# 5082_7415_mk1_v1.net
KiCad netlist of a schematic drawn in EAGLE
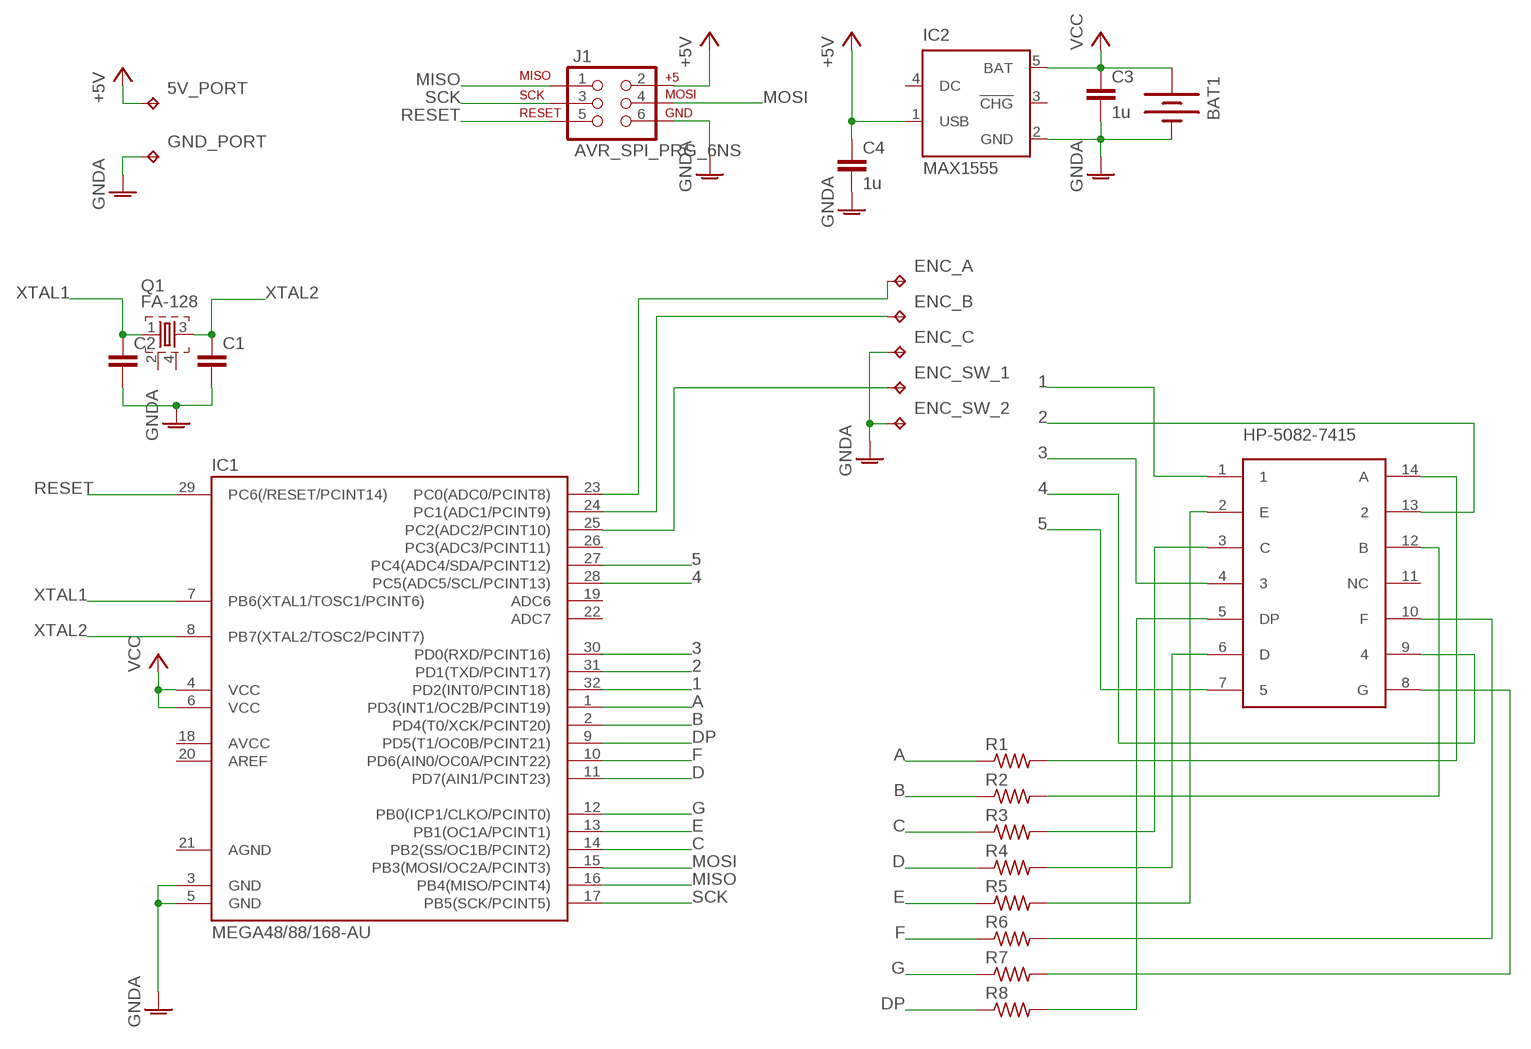
[diagram p0: schematic, sheet 1]

(export (version "E")
  (design (tool "Eeschema 10.0.6"))
  (components
    (comp (ref "5V_PORT")
      (value "TPB2,54")
      (footprint "eagle-import:B2,54")
      (libsource (lib "eagle-import") (part "TPB2,54"))
    )
    (comp (ref "BAT1")
      (value "BATTERY245MM")
      (footprint "eagle-import:BATTCON_245MM")
      (libsource (lib "eagle-import") (part "BATTERY245MM"))
    )
    (comp (ref "C1")
      (value "C-EUC0805")
      (footprint "eagle-import:C0805")
      (libsource (lib "eagle-import") (part "C-EUC0805"))
    )
    (comp (ref "C2")
      (value "C-EUC0805")
      (footprint "eagle-import:C0805")
      (libsource (lib "eagle-import") (part "C-EUC0805"))
    )
    (comp (ref "C3")
      (value "1u")
      (footprint "eagle-import:C0805")
      (libsource (lib "eagle-import") (part "C-EUC0805"))
    )
    (comp (ref "C4")
      (value "1u")
      (footprint "eagle-import:C0805")
      (libsource (lib "eagle-import") (part "C-EUC0805"))
    )
    (comp (ref "ENC_A")
      (value "TPTP20SQ")
      (footprint "eagle-import:TP20SQ")
      (libsource (lib "eagle-import") (part "TPTP20SQ"))
    )
    (comp (ref "ENC_B")
      (value "TPTP20SQ")
      (footprint "eagle-import:TP20SQ")
      (libsource (lib "eagle-import") (part "TPTP20SQ"))
    )
    (comp (ref "ENC_C")
      (value "TPTP20SQ")
      (footprint "eagle-import:TP20SQ")
      (libsource (lib "eagle-import") (part "TPTP20SQ"))
    )
    (comp (ref "ENC_SW_1")
      (value "TPTP20SQ")
      (footprint "eagle-import:TP20SQ")
      (libsource (lib "eagle-import") (part "TPTP20SQ"))
    )
    (comp (ref "ENC_SW_2")
      (value "TPTP20SQ")
      (footprint "eagle-import:TP20SQ")
      (libsource (lib "eagle-import") (part "TPTP20SQ"))
    )
    (comp (ref "GND_PORT")
      (value "TPB2,54")
      (footprint "eagle-import:B2,54")
      (libsource (lib "eagle-import") (part "TPB2,54"))
    )
    (comp (ref "IC1")
      (value "MEGA48/88/168-AU")
      (footprint "eagle-import:TQFP32-08")
      (libsource (lib "eagle-import") (part "MEGA48/88/168-AU"))
    )
    (comp (ref "IC2")
      (value "MAX1555")
      (footprint "eagle-import:SOT23-5L")
      (fields (field (name "MF") "MAXIM") (field (name "MPN") "MAX1555EZK+T"))
      (libsource (lib "eagle-import") (part "MAX1555"))
    )
    (comp (ref "J1")
      (value "AVR_SPI_PRG_6NS")
      (footprint "eagle-import:2X3-NS")
      (libsource (lib "eagle-import") (part "AVR_SPI_PRG_6NS"))
    )
    (comp (ref "Q1")
      (value "FA-128")
      (footprint "eagle-import:FA-128")
      (libsource (lib "eagle-import") (part "FA-128"))
    )
    (comp (ref "R1")
      (value "R-US_M0805")
      (footprint "eagle-import:M0805")
      (libsource (lib "eagle-import") (part "R-US_M0805"))
    )
    (comp (ref "R2")
      (value "R-US_M0805")
      (footprint "eagle-import:M0805")
      (libsource (lib "eagle-import") (part "R-US_M0805"))
    )
    (comp (ref "R3")
      (value "R-US_M0805")
      (footprint "eagle-import:M0805")
      (libsource (lib "eagle-import") (part "R-US_M0805"))
    )
    (comp (ref "R4")
      (value "R-US_M0805")
      (footprint "eagle-import:M0805")
      (libsource (lib "eagle-import") (part "R-US_M0805"))
    )
    (comp (ref "R5")
      (value "R-US_M0805")
      (footprint "eagle-import:M0805")
      (libsource (lib "eagle-import") (part "R-US_M0805"))
    )
    (comp (ref "R6")
      (value "R-US_M0805")
      (footprint "eagle-import:M0805")
      (libsource (lib "eagle-import") (part "R-US_M0805"))
    )
    (comp (ref "R7")
      (value "R-US_M0805")
      (footprint "eagle-import:M0805")
      (libsource (lib "eagle-import") (part "R-US_M0805"))
    )
    (comp (ref "R8")
      (value "R-US_M0805")
      (footprint "eagle-import:M0805")
      (libsource (lib "eagle-import") (part "R-US_M0805"))
    )
    (comp (ref "U$1")
      (value "HP-5082-7415")
      (footprint "eagle-import:DIL14")
      (libsource (lib "eagle-import") (part "HP-5082-7415"))
    )
  )
  (nets
    (net (code "1") (name "+5V") (class "Default")
      (node (ref "5V_PORT") (pin "TP") (pinfunction "TP_TP") (pintype "input"))
      (node (ref "C4") (pin "1") (pinfunction "1_1") (pintype "passive"))
      (node (ref "IC2") (pin "1") (pinfunction "USB_1") (pintype "input"))
      (node (ref "J1") (pin "2") (pinfunction "2_2") (pintype "passive"))
    )
    (net (code "2") (name "/1") (class "Default")
      (node (ref "IC1") (pin "32") (pinfunction "PD2(INT0/PCINT18)_32") (pintype "bidirectional"))
      (node (ref "U$1") (pin "1") (pinfunction "1_1") (pintype "bidirectional"))
    )
    (net (code "3") (name "/2") (class "Default")
      (node (ref "IC1") (pin "31") (pinfunction "PD1(TXD/PCINT17)_31") (pintype "bidirectional"))
      (node (ref "U$1") (pin "13") (pinfunction "2_13") (pintype "bidirectional"))
    )
    (net (code "4") (name "/3") (class "Default")
      (node (ref "IC1") (pin "30") (pinfunction "PD0(RXD/PCINT16)_30") (pintype "bidirectional"))
      (node (ref "U$1") (pin "4") (pinfunction "3_4") (pintype "bidirectional"))
    )
    (net (code "5") (name "/4") (class "Default")
      (node (ref "IC1") (pin "28") (pinfunction "PC5(ADC5/SCL/PCINT13)_28") (pintype "bidirectional"))
      (node (ref "U$1") (pin "9") (pinfunction "4_9") (pintype "bidirectional"))
    )
    (net (code "6") (name "/5") (class "Default")
      (node (ref "IC1") (pin "27") (pinfunction "PC4(ADC4/SDA/PCINT12)_27") (pintype "bidirectional"))
      (node (ref "U$1") (pin "7") (pinfunction "5_7") (pintype "bidirectional"))
    )
    (net (code "7") (name "/A") (class "Default")
      (node (ref "IC1") (pin "1") (pinfunction "PD3(INT1/OC2B/PCINT19)_1") (pintype "bidirectional"))
      (node (ref "R1") (pin "1") (pinfunction "1_1") (pintype "passive"))
    )
    (net (code "8") (name "/AGND") (class "Default")
      (node (ref "IC1") (pin "21") (pinfunction "AGND_21") (pintype "power_in"))
    )
    (net (code "9") (name "/B") (class "Default")
      (node (ref "IC1") (pin "2") (pinfunction "PD4(T0/XCK/PCINT20)_2") (pintype "bidirectional"))
      (node (ref "R2") (pin "1") (pinfunction "1_1") (pintype "passive"))
    )
    (net (code "10") (name "/C") (class "Default")
      (node (ref "IC1") (pin "14") (pinfunction "PB2(SS/OC1B/PCINT2)_14") (pintype "bidirectional"))
      (node (ref "R3") (pin "1") (pinfunction "1_1") (pintype "passive"))
    )
    (net (code "11") (name "/D") (class "Default")
      (node (ref "IC1") (pin "11") (pinfunction "PD7(AIN1/PCINT23)_11") (pintype "bidirectional"))
      (node (ref "R4") (pin "1") (pinfunction "1_1") (pintype "passive"))
    )
    (net (code "12") (name "/DP") (class "Default")
      (node (ref "IC1") (pin "9") (pinfunction "PD5(T1/OC0B/PCINT21)_9") (pintype "bidirectional"))
      (node (ref "R8") (pin "1") (pinfunction "1_1") (pintype "passive"))
    )
    (net (code "13") (name "/E") (class "Default")
      (node (ref "IC1") (pin "13") (pinfunction "PB1(OC1A/PCINT1)_13") (pintype "bidirectional"))
      (node (ref "R5") (pin "1") (pinfunction "1_1") (pintype "passive"))
    )
    (net (code "14") (name "/F") (class "Default")
      (node (ref "IC1") (pin "10") (pinfunction "PD6(AIN0/OC0A/PCINT22)_10") (pintype "bidirectional"))
      (node (ref "R6") (pin "1") (pinfunction "1_1") (pintype "passive"))
    )
    (net (code "15") (name "/G") (class "Default")
      (node (ref "IC1") (pin "12") (pinfunction "PB0(ICP1/CLKO/PCINT0)_12") (pintype "bidirectional"))
      (node (ref "R7") (pin "1") (pinfunction "1_1") (pintype "passive"))
    )
    (net (code "16") (name "/MISO") (class "Default")
      (node (ref "IC1") (pin "16") (pinfunction "PB4(MISO/PCINT4)_16") (pintype "bidirectional"))
      (node (ref "J1") (pin "1") (pinfunction "1_1") (pintype "passive"))
    )
    (net (code "17") (name "/MOSI") (class "Default")
      (node (ref "IC1") (pin "15") (pinfunction "PB3(MOSI/OC2A/PCINT3)_15") (pintype "bidirectional"))
      (node (ref "J1") (pin "4") (pinfunction "4_4") (pintype "passive"))
    )
    (net (code "18") (name "/RESET") (class "Default")
      (node (ref "IC1") (pin "29") (pinfunction "PC6(/RESET/PCINT14)_29") (pintype "bidirectional"))
      (node (ref "J1") (pin "5") (pinfunction "5_5") (pintype "passive"))
    )
    (net (code "19") (name "/SCK") (class "Default")
      (node (ref "IC1") (pin "17") (pinfunction "PB5(SCK/PCINT5)_17") (pintype "bidirectional"))
      (node (ref "J1") (pin "3") (pinfunction "3_3") (pintype "passive"))
    )
    (net (code "20") (name "/XTAL1") (class "Default")
      (node (ref "C2") (pin "1") (pinfunction "1_1") (pintype "passive"))
      (node (ref "IC1") (pin "7") (pinfunction "PB6(XTAL1/TOSC1/PCINT6)_7") (pintype "bidirectional"))
      (node (ref "Q1") (pin "1") (pinfunction "1_1") (pintype "passive"))
    )
    (net (code "21") (name "/XTAL2") (class "Default")
      (node (ref "C1") (pin "1") (pinfunction "1_1") (pintype "passive"))
      (node (ref "IC1") (pin "8") (pinfunction "PB7(XTAL2/TOSC2/PCINT7)_8") (pintype "bidirectional"))
      (node (ref "Q1") (pin "3") (pinfunction "3_3") (pintype "passive"))
    )
    (net (code "22") (name "GNDA") (class "Default")
      (node (ref "BAT1") (pin "2") (pinfunction "-_2") (pintype "power_in"))
      (node (ref "C1") (pin "2") (pinfunction "2_2") (pintype "passive"))
      (node (ref "C2") (pin "2") (pinfunction "2_2") (pintype "passive"))
      (node (ref "C3") (pin "2") (pinfunction "2_2") (pintype "passive"))
      (node (ref "C4") (pin "2") (pinfunction "2_2") (pintype "passive"))
      (node (ref "ENC_C") (pin "TP") (pinfunction "TP_TP") (pintype "input"))
      (node (ref "ENC_SW_2") (pin "TP") (pinfunction "TP_TP") (pintype "input"))
      (node (ref "GND_PORT") (pin "TP") (pinfunction "TP_TP") (pintype "input"))
      (node (ref "IC1") (pin "3") (pinfunction "GND_3") (pintype "power_in"))
      (node (ref "IC1") (pin "5") (pinfunction "GND_5") (pintype "power_in"))
      (node (ref "IC2") (pin "2") (pinfunction "GND_2") (pintype "power_in"))
      (node (ref "J1") (pin "6") (pinfunction "6_6") (pintype "passive"))
    )
    (net (code "23") (name "Net-(IC1-PC0(ADC0{slash}PCINT8))") (class "Default")
      (node (ref "ENC_A") (pin "TP") (pinfunction "TP_TP") (pintype "input"))
      (node (ref "IC1") (pin "23") (pinfunction "PC0(ADC0/PCINT8)_23") (pintype "bidirectional"))
    )
    (net (code "24") (name "Net-(IC1-PC1(ADC1{slash}PCINT9))") (class "Default")
      (node (ref "ENC_B") (pin "TP") (pinfunction "TP_TP") (pintype "input"))
      (node (ref "IC1") (pin "24") (pinfunction "PC1(ADC1/PCINT9)_24") (pintype "bidirectional"))
    )
    (net (code "25") (name "Net-(IC1-PC2(ADC2{slash}PCINT10))") (class "Default")
      (node (ref "ENC_SW_1") (pin "TP") (pinfunction "TP_TP") (pintype "input"))
      (node (ref "IC1") (pin "25") (pinfunction "PC2(ADC2/PCINT10)_25") (pintype "bidirectional"))
    )
    (net (code "26") (name "Net-(U$1-A)") (class "Default")
      (node (ref "R1") (pin "2") (pinfunction "2_2") (pintype "passive"))
      (node (ref "U$1") (pin "14") (pinfunction "A_14") (pintype "bidirectional"))
    )
    (net (code "27") (name "Net-(U$1-B)") (class "Default")
      (node (ref "R2") (pin "2") (pinfunction "2_2") (pintype "passive"))
      (node (ref "U$1") (pin "12") (pinfunction "B_12") (pintype "bidirectional"))
    )
    (net (code "28") (name "Net-(U$1-C)") (class "Default")
      (node (ref "R3") (pin "2") (pinfunction "2_2") (pintype "passive"))
      (node (ref "U$1") (pin "3") (pinfunction "C_3") (pintype "bidirectional"))
    )
    (net (code "29") (name "Net-(U$1-D)") (class "Default")
      (node (ref "R4") (pin "2") (pinfunction "2_2") (pintype "passive"))
      (node (ref "U$1") (pin "6") (pinfunction "D_6") (pintype "bidirectional"))
    )
    (net (code "30") (name "Net-(U$1-DP)") (class "Default")
      (node (ref "R8") (pin "2") (pinfunction "2_2") (pintype "passive"))
      (node (ref "U$1") (pin "5") (pinfunction "DP_5") (pintype "bidirectional"))
    )
    (net (code "31") (name "Net-(U$1-E)") (class "Default")
      (node (ref "R5") (pin "2") (pinfunction "2_2") (pintype "passive"))
      (node (ref "U$1") (pin "2") (pinfunction "E_2") (pintype "bidirectional"))
    )
    (net (code "32") (name "Net-(U$1-F)") (class "Default")
      (node (ref "R6") (pin "2") (pinfunction "2_2") (pintype "passive"))
      (node (ref "U$1") (pin "10") (pinfunction "F_10") (pintype "bidirectional"))
    )
    (net (code "33") (name "Net-(U$1-G)") (class "Default")
      (node (ref "R7") (pin "2") (pinfunction "2_2") (pintype "passive"))
      (node (ref "U$1") (pin "8") (pinfunction "G_8") (pintype "bidirectional"))
    )
    (net (code "34") (name "VCC") (class "Default")
      (node (ref "BAT1") (pin "1") (pinfunction "+_1") (pintype "power_in"))
      (node (ref "C3") (pin "1") (pinfunction "1_1") (pintype "passive"))
      (node (ref "IC1") (pin "4") (pinfunction "VCC_4") (pintype "power_in"))
      (node (ref "IC1") (pin "6") (pinfunction "VCC_6") (pintype "power_in"))
      (node (ref "IC2") (pin "5") (pinfunction "BAT_5") (pintype "passive"))
    )
    (net (code "35") (name "unconnected-(IC1-ADC6-Pad19)") (class "Default")
      (node (ref "IC1") (pin "19") (pinfunction "ADC6_19") (pintype "passive"))
    )
    (net (code "36") (name "unconnected-(IC1-ADC7-Pad22)") (class "Default")
      (node (ref "IC1") (pin "22") (pinfunction "ADC7_22") (pintype "passive"))
    )
    (net (code "37") (name "unconnected-(IC1-AREF-Pad20)") (class "Default")
      (node (ref "IC1") (pin "20") (pinfunction "AREF_20") (pintype "passive"))
    )
    (net (code "38") (name "unconnected-(IC1-AVCC-Pad18)") (class "Default")
      (node (ref "IC1") (pin "18") (pinfunction "AVCC_18") (pintype "passive"))
    )
    (net (code "39") (name "unconnected-(IC1-PC3(ADC3{slash}PCINT11)-Pad26)") (class "Default")
      (node (ref "IC1") (pin "26") (pinfunction "PC3(ADC3/PCINT11)_26") (pintype "bidirectional"))
    )
    (net (code "40") (name "unconnected-(IC2-DC-Pad4)") (class "Default")
      (node (ref "IC2") (pin "4") (pinfunction "DC_4") (pintype "input"))
    )
    (net (code "41") (name "unconnected-(IC2-~{CHG}-Pad3)") (class "Default")
      (node (ref "IC2") (pin "3") (pinfunction "~{CHG}_3") (pintype "output"))
    )
    (net (code "42") (name "unconnected-(Q1-Pad2)") (class "Default")
      (node (ref "Q1") (pin "2") (pinfunction "2_2") (pintype "passive"))
    )
    (net (code "43") (name "unconnected-(Q1-Pad4)") (class "Default")
      (node (ref "Q1") (pin "4") (pinfunction "4_4") (pintype "passive"))
    )
    (net (code "44") (name "unconnected-(U$1-NC-Pad11)") (class "Default")
      (node (ref "U$1") (pin "11") (pinfunction "NC_11") (pintype "bidirectional"))
    )
  )
)
